# Analog_DP_V2.net
KiCad netlist of a schematic drawn in EAGLE
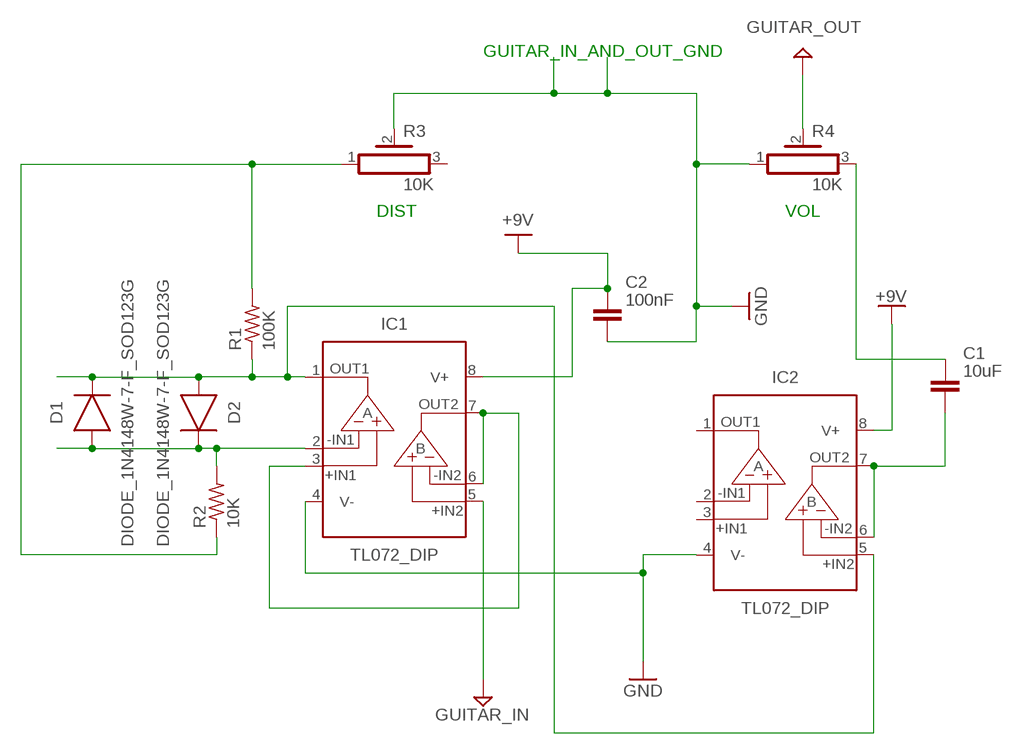
[diagram p0: schematic, sheet 1]

(export (version "E")
  (design (tool "Eeschema 10.0.6"))
  (components
    (comp (ref "C1")
      (value "10uF")
      (footprint "eagle-import:CAPRD2261W240D5080H5555B")
      (libsource (lib "eagle-import") (part "CRADIAL-55.5MM-DIA_"))
    )
    (comp (ref "C2")
      (value "100nF")
      (footprint "eagle-import:CAPRD2261W240D5080H5555B")
      (libsource (lib "eagle-import") (part "CRADIAL-55.5MM-DIA_"))
    )
    (comp (ref "D1")
      (value "DIODE_1N4148W-7-F_SOD123G")
      (footprint "eagle-import:SOD3715X135")
      (fields (field (name "MANUFACTURER") "Diodes Incorporated") (field (name "MPN") "1N4148W-7-F"))
      (libsource (lib "eagle-import") (part "DIODE__SOD123G1N4148W-7-F"))
    )
    (comp (ref "D2")
      (value "DIODE_1N4148W-7-F_SOD123G")
      (footprint "eagle-import:SOD3715X135")
      (fields (field (name "MANUFACTURER") "Diodes Incorporated") (field (name "MPN") "1N4148W-7-F"))
      (libsource (lib "eagle-import") (part "DIODE__SOD123G1N4148W-7-F"))
    )
    (comp (ref "IC1")
      (value "TL072_DIP")
      (footprint "eagle-import:DIP826W53P254L959H508Q8B")
      (fields (field (name "MANUFACTURER") "Generic"))
      (libsource (lib "eagle-import") (part "TL072_DIP"))
    )
    (comp (ref "IC2")
      (value "TL072_DIP")
      (footprint "eagle-import:DIP826W53P254L959H508Q8B")
      (fields (field (name "MANUFACTURER") "Generic"))
      (libsource (lib "eagle-import") (part "TL072_DIP"))
    )
    (comp (ref "R1")
      (value "100K")
      (footprint "eagle-import:RESAD724W46L381D178B")
      (libsource (lib "eagle-import") (part "R-USAXIAL-7.2MM-PITCH_"))
    )
    (comp (ref "R2")
      (value "10K")
      (footprint "eagle-import:RESAD724W46L381D178B")
      (libsource (lib "eagle-import") (part "R-USAXIAL-7.2MM-PITCH_"))
    )
    (comp (ref "R3")
      (value "10K")
      (footprint "eagle-import:PV36Y")
      (fields (field (name "MANUFACTURER") "BOURNS") (field (name "MPN") "PV36Y"))
      (libsource (lib "eagle-import") (part "POT_PV36Y"))
    )
    (comp (ref "R4")
      (value "10K")
      (footprint "eagle-import:PV36Y")
      (fields (field (name "MANUFACTURER") "BOURNS") (field (name "MPN") "PV36Y"))
      (libsource (lib "eagle-import") (part "POT_PV36Y"))
    )
  )
  (nets
    (net (code "1") (name "+9V") (class "Default")
      (node (ref "C2") (pin "1") (pinfunction "1_1") (pintype "passive"))
      (node (ref "IC1") (pin "8") (pinfunction "V+_8") (pintype "bidirectional"))
      (node (ref "IC2") (pin "8") (pinfunction "V+_8") (pintype "bidirectional"))
    )
    (net (code "2") (name "GND") (class "Default")
      (node (ref "C2") (pin "2") (pinfunction "2_2") (pintype "passive"))
      (node (ref "IC1") (pin "4") (pinfunction "V-_4") (pintype "bidirectional"))
      (node (ref "IC2") (pin "4") (pinfunction "V-_4") (pintype "bidirectional"))
      (node (ref "R3") (pin "2") (pinfunction "P$2_2") (pintype "passive"))
      (node (ref "R4") (pin "1") (pinfunction "P$1_1") (pintype "passive"))
    )
    (net (code "3") (name "GUITAR_IN") (class "Default")
      (node (ref "IC1") (pin "5") (pinfunction "+IN2_5") (pintype "passive"))
    )
    (net (code "4") (name "GUITAR_OUT") (class "Default")
      (node (ref "R4") (pin "2") (pinfunction "P$2_2") (pintype "passive"))
    )
    (net (code "5") (name "Net-(D1-A)") (class "Default")
      (node (ref "D1") (pin "2") (pinfunction "A_2") (pintype "passive"))
      (node (ref "D2") (pin "1") (pinfunction "C_1") (pintype "passive"))
      (node (ref "IC1") (pin "2") (pinfunction "-IN1_2") (pintype "input"))
      (node (ref "R2") (pin "2") (pinfunction "2_2") (pintype "passive"))
    )
    (net (code "6") (name "Net-(D1-C)") (class "Default")
      (node (ref "D1") (pin "1") (pinfunction "C_1") (pintype "passive"))
      (node (ref "D2") (pin "2") (pinfunction "A_2") (pintype "passive"))
      (node (ref "IC1") (pin "1") (pinfunction "OUT1_1") (pintype "passive"))
      (node (ref "IC2") (pin "5") (pinfunction "+IN2_5") (pintype "passive"))
      (node (ref "R1") (pin "1") (pinfunction "1_1") (pintype "passive"))
    )
    (net (code "7") (name "Net-(IC1-+IN1)") (class "Default")
      (node (ref "IC1") (pin "3") (pinfunction "+IN1_3") (pintype "input"))
      (node (ref "IC1") (pin "6") (pinfunction "-IN2_6") (pintype "passive"))
      (node (ref "IC1") (pin "7") (pinfunction "OUT2_7") (pintype "passive"))
    )
    (net (code "8") (name "Net-(IC2--IN2)") (class "Default")
      (node (ref "C1") (pin "2") (pinfunction "2_2") (pintype "passive"))
      (node (ref "IC2") (pin "6") (pinfunction "-IN2_6") (pintype "passive"))
      (node (ref "IC2") (pin "7") (pinfunction "OUT2_7") (pintype "passive"))
    )
    (net (code "9") (name "Net-(R3-P$1)") (class "Default")
      (node (ref "R1") (pin "2") (pinfunction "2_2") (pintype "passive"))
      (node (ref "R2") (pin "1") (pinfunction "1_1") (pintype "passive"))
      (node (ref "R3") (pin "1") (pinfunction "P$1_1") (pintype "passive"))
    )
    (net (code "10") (name "Net-(R4-P$3)") (class "Default")
      (node (ref "C1") (pin "1") (pinfunction "1_1") (pintype "passive"))
      (node (ref "R4") (pin "3") (pinfunction "P$3_3") (pintype "passive"))
    )
    (net (code "11") (name "unconnected-(IC2-+IN1-Pad3)") (class "Default")
      (node (ref "IC2") (pin "3") (pinfunction "+IN1_3") (pintype "input"))
    )
    (net (code "12") (name "unconnected-(IC2--IN1-Pad2)") (class "Default")
      (node (ref "IC2") (pin "2") (pinfunction "-IN1_2") (pintype "input"))
    )
    (net (code "13") (name "unconnected-(IC2-OUT1-Pad1)") (class "Default")
      (node (ref "IC2") (pin "1") (pinfunction "OUT1_1") (pintype "passive"))
    )
    (net (code "14") (name "unconnected-(R3-P$3-Pad3)") (class "Default")
      (node (ref "R3") (pin "3") (pinfunction "P$3_3") (pintype "passive"))
    )
  )
)
